# conn_usbc.net
KiCad netlist of a schematic drawn in Altium Designer
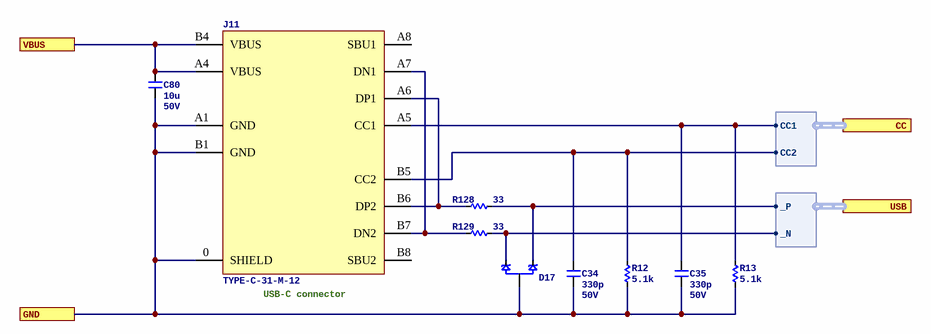
[diagram p0: conn_usbc.SchDoc]

(export (version "E")
  (design (tool "Eeschema 10.0.6"))
  (components
    (comp (ref "C34")
      (value "CL05C331JB5NNNC")
      (footprint "C0402")
      (fields
        (field (name "CAPACITANCE") "330p")
        (field (name "MANUFACTURER") "Samsung Electro-Mechanics")
        (field (name "VOLTAGE RATING") "50V")
      )
      (libsource (lib "database") (part "__template_cap"))
    )
    (comp (ref "C35")
      (value "CL05C331JB5NNNC")
      (footprint "C0402")
      (fields
        (field (name "CAPACITANCE") "330p")
        (field (name "MANUFACTURER") "Samsung Electro-Mechanics")
        (field (name "VOLTAGE RATING") "50V")
      )
      (libsource (lib "database") (part "__template_cap"))
    )
    (comp (ref "C80")
      (value "CL31B106KBHNNNE")
      (footprint "C1206")
      (fields
        (field (name "CAPACITANCE") "10u")
        (field (name "MANUFACTURER") "Samsung Electro-Mechanics")
        (field (name "VOLTAGE RATING") "50V")
      )
      (libsource (lib "database") (part "__template_cap"))
    )
    (comp (ref "D17")
      (value "PESD2USB3UX")
      (footprint "3SOT23")
      (description "DIODE ESD USB SOT-23")
      (fields (field (name "MANUFACTURER") "Nexperia USA Inc."))
      (libsource (lib "SSCP") (part "TVS_PESD2USB3UX-T"))
    )
    (comp (ref "J11")
      (value "TYPE-C-31-M-12")
      (footprint "CONN_USBC_TYPE-C-31-M-12")
      (description "5A 1 16P Female Type-C SMD USB Connectors ROHS")
      (fields (field (name "MANUFACTURER") "HRO Electronics"))
      (libsource (lib "SSCP") (part "CONN_USBC_TYPE-C-31-M-12"))
    )
    (comp (ref "R12")
      (value "5.1k")
      (footprint "R0402")
      (fields
        (field (name "TOLERANCE") "1%")
        (field (name "MANUFACTURER PART NUMBER") "0402WGF5101TCE")
        (field (name "MANUFACTURER") "UNI-ROYAL(Uniroyal Elec)")
      )
      (libsource (lib "database") (part "__template_resistor"))
    )
    (comp (ref "R13")
      (value "5.1k")
      (footprint "R0402")
      (fields
        (field (name "TOLERANCE") "1%")
        (field (name "MANUFACTURER PART NUMBER") "0402WGF5101TCE")
        (field (name "MANUFACTURER") "UNI-ROYAL(Uniroyal Elec)")
      )
      (libsource (lib "database") (part "__template_resistor"))
    )
    (comp (ref "R128")
      (value "33")
      (footprint "R0402")
      (fields
        (field (name "TOLERANCE") "1%")
        (field (name "MANUFACTURER PART NUMBER") "CRCW040233R0FKED")
        (field (name "MANUFACTURER") "Vishay Intertech")
      )
      (libsource (lib "database") (part "__template_resistor"))
    )
    (comp (ref "R129")
      (value "33")
      (footprint "R0402")
      (fields
        (field (name "TOLERANCE") "1%")
        (field (name "MANUFACTURER PART NUMBER") "CRCW040233R0FKED")
        (field (name "MANUFACTURER") "Vishay Intertech")
      )
      (libsource (lib "database") (part "__template_resistor"))
    )
  )
  (nets
    (net (code "3") (name "/GND") (class "Default")
      (node (ref "C34") (pin "2") (pintype "passive"))
      (node (ref "C35") (pin "2") (pintype "passive"))
      (node (ref "C80") (pin "2") (pintype "passive"))
      (node (ref "D17") (pin "3") (pintype "passive"))
      (node (ref "J11") (pin "0") (pinfunction "SHIELD_0") (pintype "power_in"))
      (node (ref "J11") (pin "A1") (pinfunction "GND_A1") (pintype "power_in"))
      (node (ref "J11") (pin "B1") (pinfunction "GND_B1") (pintype "power_in"))
      (node (ref "R12") (pin "2") (pintype "passive"))
      (node (ref "R13") (pin "2") (pintype "passive"))
    )
    (net (code "4") (name "/VBUS") (class "Default")
      (node (ref "C80") (pin "1") (pintype "passive"))
      (node (ref "J11") (pin "A4") (pinfunction "VBUS_A4") (pintype "power_in"))
      (node (ref "J11") (pin "B4") (pinfunction "VBUS_B4") (pintype "passive"))
    )
    (net (code "7") (name "Net-(D17-Pad1)") (class "Default")
      (node (ref "D17") (pin "1") (pintype "passive"))
      (node (ref "R128") (pin "1") (pintype "passive"))
    )
    (net (code "8") (name "Net-(D17-Pad2)") (class "Default")
      (node (ref "D17") (pin "2") (pintype "passive"))
      (node (ref "R129") (pin "1") (pintype "passive"))
    )
    (net (code "9") (name "Net-(J11-CC1)") (class "Default")
      (node (ref "C35") (pin "1") (pintype "passive"))
      (node (ref "J11") (pin "A5") (pinfunction "CC1_A5") (pintype "passive"))
      (node (ref "R13") (pin "1") (pintype "passive"))
    )
    (net (code "10") (name "Net-(J11-CC2)") (class "Default")
      (node (ref "C34") (pin "1") (pintype "passive"))
      (node (ref "J11") (pin "B5") (pinfunction "CC2_B5") (pintype "passive"))
      (node (ref "R12") (pin "1") (pintype "passive"))
    )
    (net (code "11") (name "Net-(J11-DN1)") (class "Default")
      (node (ref "J11") (pin "A7") (pinfunction "DN1_A7") (pintype "passive"))
      (node (ref "J11") (pin "B7") (pinfunction "DN2_B7") (pintype "passive"))
      (node (ref "R129") (pin "2") (pintype "passive"))
    )
    (net (code "12") (name "Net-(J11-DP1)") (class "Default")
      (node (ref "J11") (pin "A6") (pinfunction "DP1_A6") (pintype "passive"))
      (node (ref "J11") (pin "B6") (pinfunction "DP2_B6") (pintype "passive"))
      (node (ref "R128") (pin "2") (pintype "passive"))
    )
    (net (code "13") (name "unconnected-(J11-SBU1-PadA8)") (class "Default")
      (node (ref "J11") (pin "A8") (pinfunction "SBU1_A8") (pintype "passive"))
    )
    (net (code "14") (name "unconnected-(J11-SBU2-PadB8)") (class "Default")
      (node (ref "J11") (pin "B8") (pinfunction "SBU2_B8") (pintype "passive"))
    )
  )
)
